# CanBus12apr.net
KiCad netlist of a schematic drawn in EAGLE
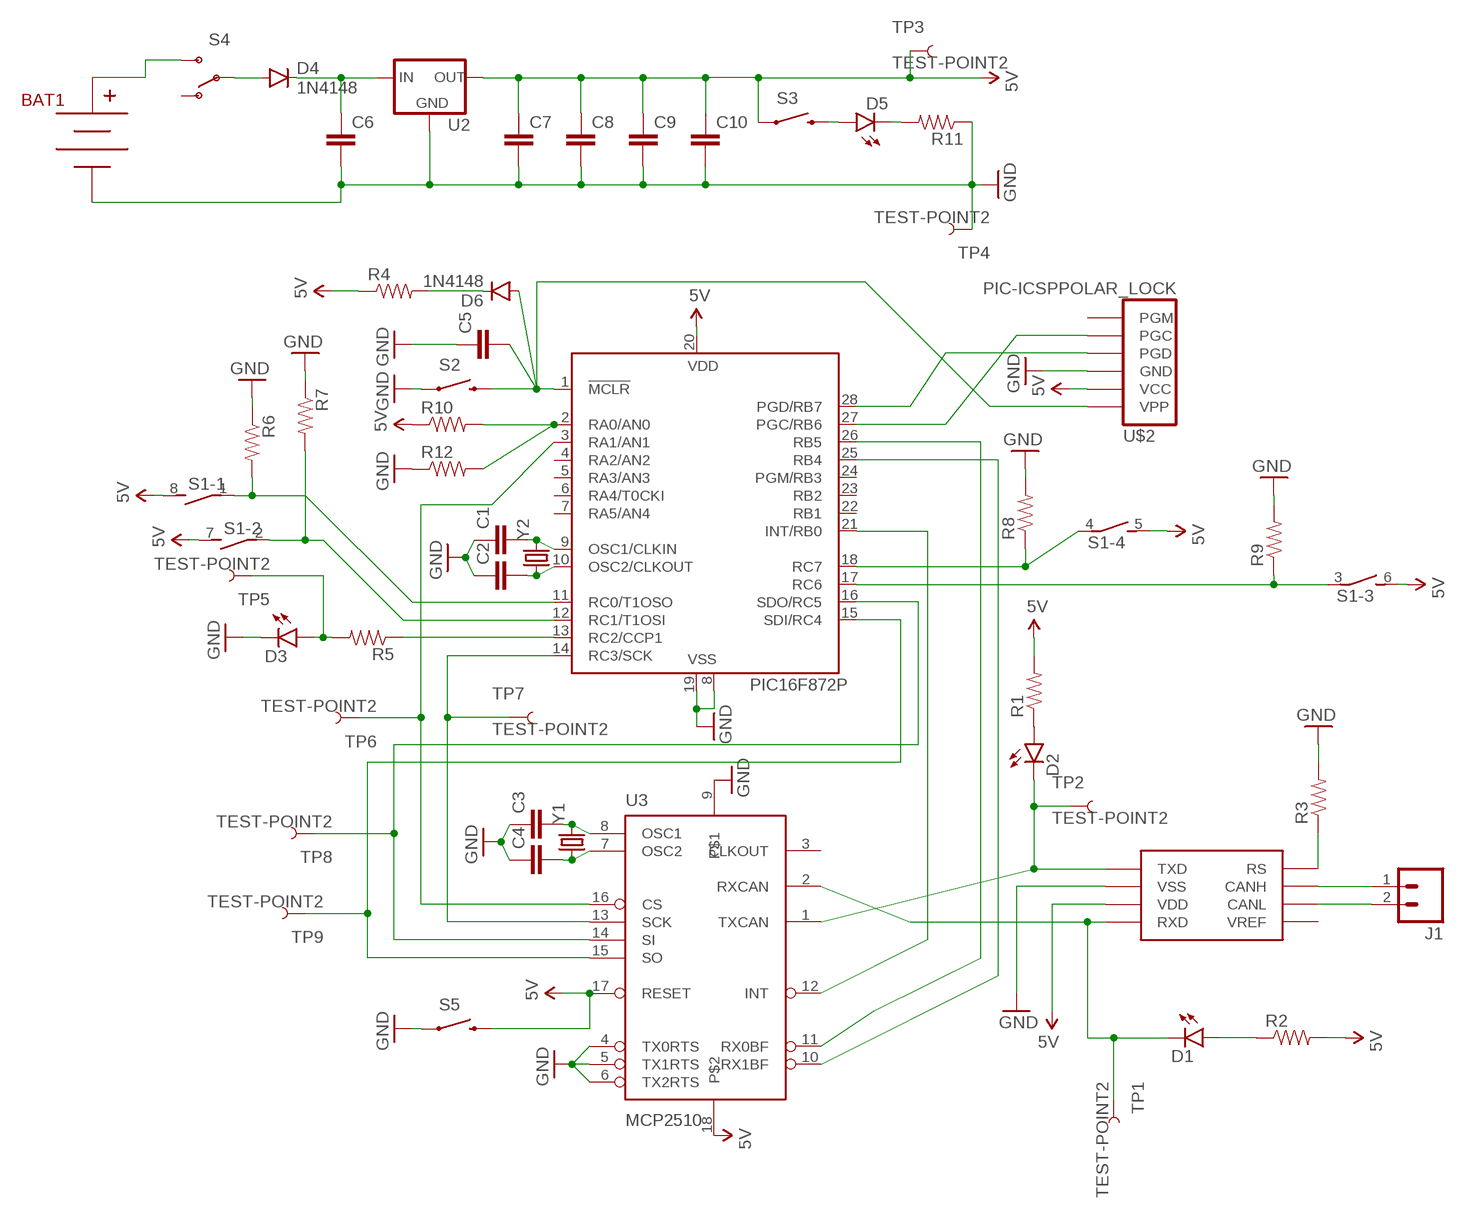
[diagram p0: schematic, sheet 1]

(export (version "E")
  (design (tool "Eeschema 10.0.6"))
  (components
    (comp (ref "BAT1")
      (value "BC9VPC")
      (footprint "eagle-import:BC9VPC")
      (libsource (lib "eagle-import") (part "BC9VPC"))
    )
    (comp (ref "C1")
      (value "CAPPTH")
      (footprint "eagle-import:CAP-PTH-SMALL")
      (libsource (lib "eagle-import") (part "CAPPTH"))
    )
    (comp (ref "C2")
      (value "CAPPTH")
      (footprint "eagle-import:CAP-PTH-SMALL")
      (libsource (lib "eagle-import") (part "CAPPTH"))
    )
    (comp (ref "C3")
      (value "CAPPTH")
      (footprint "eagle-import:CAP-PTH-SMALL")
      (libsource (lib "eagle-import") (part "CAPPTH"))
    )
    (comp (ref "C4")
      (value "CAPPTH")
      (footprint "eagle-import:CAP-PTH-SMALL")
      (libsource (lib "eagle-import") (part "CAPPTH"))
    )
    (comp (ref "C5")
      (value "CAPPTH")
      (footprint "eagle-import:CAP-PTH-SMALL")
      (libsource (lib "eagle-import") (part "CAPPTH"))
    )
    (comp (ref "C6")
      (value "CAPPTH")
      (footprint "eagle-import:CAP-PTH-SMALL")
      (libsource (lib "eagle-import") (part "CAPPTH"))
    )
    (comp (ref "C7")
      (value "CAPPTH")
      (footprint "eagle-import:CAP-PTH-SMALL")
      (libsource (lib "eagle-import") (part "CAPPTH"))
    )
    (comp (ref "C8")
      (value "CAPPTH")
      (footprint "eagle-import:CAP-PTH-SMALL")
      (libsource (lib "eagle-import") (part "CAPPTH"))
    )
    (comp (ref "C9")
      (value "CAPPTH")
      (footprint "eagle-import:CAP-PTH-SMALL")
      (libsource (lib "eagle-import") (part "CAPPTH"))
    )
    (comp (ref "C10")
      (value "CAPPTH")
      (footprint "eagle-import:CAP-PTH-SMALL")
      (libsource (lib "eagle-import") (part "CAPPTH"))
    )
    (comp (ref "D1")
      (value "LED5MM")
      (footprint "eagle-import:LED5MM")
      (libsource (lib "eagle-import") (part "LED5MM"))
    )
    (comp (ref "D2")
      (value "LED5MM")
      (footprint "eagle-import:LED5MM")
      (libsource (lib "eagle-import") (part "LED5MM"))
    )
    (comp (ref "D3")
      (value "LED5MM")
      (footprint "eagle-import:LED5MM")
      (libsource (lib "eagle-import") (part "LED5MM"))
    )
    (comp (ref "D4")
      (value "1N4148")
      (footprint "eagle-import:DIODE-1N4148-KIT")
      (libsource (lib "eagle-import") (part "DIODEKIT"))
    )
    (comp (ref "D5")
      (value "LED5MM")
      (footprint "eagle-import:LED5MM")
      (libsource (lib "eagle-import") (part "LED5MM"))
    )
    (comp (ref "D6")
      (value "1N4148")
      (footprint "eagle-import:DIODE-1N4148-KIT")
      (libsource (lib "eagle-import") (part "DIODEKIT"))
    )
    (comp (ref "IC1")
      (value "PIC16F872P")
      (footprint "eagle-import:DIL28-3")
      (fields (field (name "MF") "MICROCHIP") (field (name "MPN") "PIC16F872-I/SP"))
      (libsource (lib "eagle-import") (part "PIC16872PF"))
    )
    (comp (ref "J1")
      (value "M02PTH")
      (footprint "eagle-import:1X02")
      (libsource (lib "eagle-import") (part "M02PTH"))
    )
    (comp (ref "R1")
      (value "RESISTOREZ")
      (footprint "eagle-import:AXIAL-0.3EZ")
      (libsource (lib "eagle-import") (part "RESISTOREZ"))
    )
    (comp (ref "R2")
      (value "RESISTOREZ")
      (footprint "eagle-import:AXIAL-0.3EZ")
      (libsource (lib "eagle-import") (part "RESISTOREZ"))
    )
    (comp (ref "R3")
      (value "RESISTOREZ")
      (footprint "eagle-import:AXIAL-0.3EZ")
      (libsource (lib "eagle-import") (part "RESISTOREZ"))
    )
    (comp (ref "R4")
      (value "RESISTOREZ")
      (footprint "eagle-import:AXIAL-0.3EZ")
      (libsource (lib "eagle-import") (part "RESISTOREZ"))
    )
    (comp (ref "R5")
      (value "RESISTOREZ")
      (footprint "eagle-import:AXIAL-0.3EZ")
      (libsource (lib "eagle-import") (part "RESISTOREZ"))
    )
    (comp (ref "R6")
      (value "RESISTOREZ")
      (footprint "eagle-import:AXIAL-0.3EZ")
      (libsource (lib "eagle-import") (part "RESISTOREZ"))
    )
    (comp (ref "R7")
      (value "RESISTOREZ")
      (footprint "eagle-import:AXIAL-0.3EZ")
      (libsource (lib "eagle-import") (part "RESISTOREZ"))
    )
    (comp (ref "R8")
      (value "RESISTOREZ")
      (footprint "eagle-import:AXIAL-0.3EZ")
      (libsource (lib "eagle-import") (part "RESISTOREZ"))
    )
    (comp (ref "R9")
      (value "RESISTOREZ")
      (footprint "eagle-import:AXIAL-0.3EZ")
      (libsource (lib "eagle-import") (part "RESISTOREZ"))
    )
    (comp (ref "R10")
      (value "RESISTOREZ")
      (footprint "eagle-import:AXIAL-0.3EZ")
      (libsource (lib "eagle-import") (part "RESISTOREZ"))
    )
    (comp (ref "R11")
      (value "RESISTOREZ")
      (footprint "eagle-import:AXIAL-0.3EZ")
      (libsource (lib "eagle-import") (part "RESISTOREZ"))
    )
    (comp (ref "R12")
      (value "RESISTORAXIAL-0.3")
      (footprint "eagle-import:AXIAL-0.3")
      (libsource (lib "eagle-import") (part "SparkFun-Resistors_RESISTORAXIAL-0.3"))
    )
    (comp (ref "S1")
      (value "DIP04S")
      (footprint "eagle-import:DIP04S")
      (libsource (lib "eagle-import") (part "DIP04S"))
    )
    (comp (ref "S2")
      (value "SWITCH-MOMENTARY-2PTH")
      (footprint "eagle-import:TACTILE-PTH")
      (libsource (lib "eagle-import") (part "SWITCH-MOMENTARY-2PTH"))
    )
    (comp (ref "S3")
      (value "SWITCH-MOMENTARY-2PTH")
      (footprint "eagle-import:TACTILE-PTH")
      (libsource (lib "eagle-import") (part "SWITCH-MOMENTARY-2PTH"))
    )
    (comp (ref "S4")
      (value "SWITCH-SPDTKIT")
      (footprint "eagle-import:SWITCH-SPDT_KIT")
      (libsource (lib "eagle-import") (part "SWITCH-SPDTKIT"))
    )
    (comp (ref "S5")
      (value "SWITCH-MOMENTARY-2PTH")
      (footprint "eagle-import:TACTILE-PTH")
      (libsource (lib "eagle-import") (part "SWITCH-MOMENTARY-2PTH"))
    )
    (comp (ref "TP1")
      (value "TEST-POINT2")
      (footprint "eagle-import:PAD.02X.02")
      (libsource (lib "eagle-import") (part "TEST-POINT2"))
    )
    (comp (ref "TP2")
      (value "TEST-POINT2")
      (footprint "eagle-import:PAD.02X.02")
      (libsource (lib "eagle-import") (part "TEST-POINT2"))
    )
    (comp (ref "TP3")
      (value "TEST-POINT2")
      (footprint "eagle-import:PAD.02X.02")
      (libsource (lib "eagle-import") (part "TEST-POINT2"))
    )
    (comp (ref "TP4")
      (value "TEST-POINT2")
      (footprint "eagle-import:PAD.02X.02")
      (libsource (lib "eagle-import") (part "TEST-POINT2"))
    )
    (comp (ref "TP5")
      (value "TEST-POINT2")
      (footprint "eagle-import:PAD.02X.02")
      (libsource (lib "eagle-import") (part "TEST-POINT2"))
    )
    (comp (ref "TP6")
      (value "TEST-POINT2")
      (footprint "eagle-import:PAD.02X.02")
      (libsource (lib "eagle-import") (part "TEST-POINT2"))
    )
    (comp (ref "TP7")
      (value "TEST-POINT2")
      (footprint "eagle-import:PAD.02X.02")
      (libsource (lib "eagle-import") (part "TEST-POINT2"))
    )
    (comp (ref "TP8")
      (value "TEST-POINT2")
      (footprint "eagle-import:PAD.02X.02")
      (libsource (lib "eagle-import") (part "TEST-POINT2"))
    )
    (comp (ref "TP9")
      (value "TEST-POINT2")
      (footprint "eagle-import:PAD.02X.02")
      (libsource (lib "eagle-import") (part "TEST-POINT2"))
    )
    (comp (ref "U$1")
      (value "MCP2551")
      (footprint "eagle-import:MCP2551")
      (libsource (lib "eagle-import") (part "MCP2551"))
    )
    (comp (ref "U$2")
      (value "PIC-ICSPPOLAR_LOCK")
      (footprint "eagle-import:MOLEX-1X6_LOCK")
      (libsource (lib "eagle-import") (part "PIC-ICSPPOLAR_LOCK"))
    )
    (comp (ref "U2")
      (value "V_REG_78XXSIDE")
      (footprint "eagle-import:78XXL")
      (libsource (lib "eagle-import") (part "V_REG_78XXSIDE"))
    )
    (comp (ref "U3")
      (value "MCP2510")
      (footprint "eagle-import:DIL18")
      (libsource (lib "eagle-import") (part "MCP2510"))
    )
    (comp (ref "Y1")
      (value "CRYSTALHC49UV")
      (footprint "eagle-import:HC49U-V")
      (libsource (lib "eagle-import") (part "CRYSTALHC49UV"))
    )
    (comp (ref "Y2")
      (value "CRYSTALHC49UV")
      (footprint "eagle-import:HC49U-V")
      (libsource (lib "eagle-import") (part "CRYSTALHC49UV"))
    )
  )
  (nets
    (net (code "1") (name "5V") (class "Default")
      (node (ref "C10") (pin "1") (pinfunction "1_1") (pintype "passive"))
      (node (ref "C7") (pin "1") (pinfunction "1_1") (pintype "passive"))
      (node (ref "C8") (pin "1") (pinfunction "1_1") (pintype "passive"))
      (node (ref "C9") (pin "1") (pinfunction "1_1") (pintype "passive"))
      (node (ref "IC1") (pin "20") (pinfunction "VDD_20") (pintype "power_in"))
      (node (ref "R1") (pin "P$2") (pinfunction "2_P$2") (pintype "passive"))
      (node (ref "R10") (pin "P$1") (pinfunction "1_P$1") (pintype "passive"))
      (node (ref "R2") (pin "P$2") (pinfunction "2_P$2") (pintype "passive"))
      (node (ref "R4") (pin "P$1") (pinfunction "1_P$1") (pintype "passive"))
      (node (ref "S1") (pin "5") (pinfunction "2_5") (pintype "passive"))
      (node (ref "S1") (pin "6") (pinfunction "2_6") (pintype "passive"))
      (node (ref "S1") (pin "7") (pinfunction "2_7") (pintype "passive"))
      (node (ref "S1") (pin "8") (pinfunction "2_8") (pintype "passive"))
      (node (ref "S3") (pin "1") (pinfunction "1_1") (pintype "passive"))
      (node (ref "S5") (pin "3") (pinfunction "2_3") (pintype "passive"))
      (node (ref "TP3") (pin "P$1") (pinfunction "1_P$1") (pintype "bidirectional"))
      (node (ref "U$1") (pin "VDD") (pinfunction "VDD_VDD") (pintype "bidirectional"))
      (node (ref "U$2") (pin "5") (pinfunction "VCC_5") (pintype "bidirectional"))
      (node (ref "U2") (pin "OUT") (pinfunction "OUT_OUT") (pintype "passive"))
      (node (ref "U3") (pin "17") (pinfunction "RESET_17") (pintype "input"))
      (node (ref "U3") (pin "18") (pinfunction "P$2_18") (pintype "bidirectional"))
    )
    (net (code "2") (name "GND") (class "Default")
      (node (ref "BAT1") (pin "V-") (pinfunction "V-_V-") (pintype "bidirectional"))
      (node (ref "C1") (pin "1") (pinfunction "1_1") (pintype "passive"))
      (node (ref "C10") (pin "2") (pinfunction "2_2") (pintype "passive"))
      (node (ref "C2") (pin "1") (pinfunction "1_1") (pintype "passive"))
      (node (ref "C3") (pin "1") (pinfunction "1_1") (pintype "passive"))
      (node (ref "C4") (pin "1") (pinfunction "1_1") (pintype "passive"))
      (node (ref "C5") (pin "1") (pinfunction "1_1") (pintype "passive"))
      (node (ref "C6") (pin "2") (pinfunction "2_2") (pintype "passive"))
      (node (ref "C7") (pin "2") (pinfunction "2_2") (pintype "passive"))
      (node (ref "C8") (pin "2") (pinfunction "2_2") (pintype "passive"))
      (node (ref "C9") (pin "2") (pinfunction "2_2") (pintype "passive"))
      (node (ref "D3") (pin "K") (pinfunction "C_K") (pintype "passive"))
      (node (ref "IC1") (pin "19") (pinfunction "VSS_19") (pintype "power_in"))
      (node (ref "IC1") (pin "8") (pinfunction "VSS_8") (pintype "power_in"))
      (node (ref "R11") (pin "P$1") (pinfunction "1_P$1") (pintype "passive"))
      (node (ref "R12") (pin "P$1") (pinfunction "1_P$1") (pintype "passive"))
      (node (ref "R3") (pin "P$2") (pinfunction "2_P$2") (pintype "passive"))
      (node (ref "R6") (pin "P$1") (pinfunction "1_P$1") (pintype "passive"))
      (node (ref "R7") (pin "P$1") (pinfunction "1_P$1") (pintype "passive"))
      (node (ref "R8") (pin "P$2") (pinfunction "2_P$2") (pintype "passive"))
      (node (ref "R9") (pin "P$2") (pinfunction "2_P$2") (pintype "passive"))
      (node (ref "S2") (pin "1") (pinfunction "1_1") (pintype "passive"))
      (node (ref "S5") (pin "1") (pinfunction "1_1") (pintype "passive"))
      (node (ref "TP4") (pin "P$1") (pinfunction "1_P$1") (pintype "bidirectional"))
      (node (ref "U$1") (pin "VSS") (pinfunction "VSS_VSS") (pintype "bidirectional"))
      (node (ref "U$2") (pin "4") (pinfunction "GND_4") (pintype "bidirectional"))
      (node (ref "U2") (pin "GND") (pinfunction "GND_GND") (pintype "input"))
      (node (ref "U3") (pin "4") (pinfunction "TX0RTS_4") (pintype "input"))
      (node (ref "U3") (pin "5") (pinfunction "TX1RTS_5") (pintype "input"))
      (node (ref "U3") (pin "6") (pinfunction "TX2RTS_6") (pintype "input"))
      (node (ref "U3") (pin "9") (pinfunction "P$1_9") (pintype "bidirectional"))
    )
    (net (code "3") (name "Net-(C6-Pad1)") (class "Default")
      (node (ref "C6") (pin "1") (pinfunction "1_1") (pintype "passive"))
      (node (ref "D4") (pin "C") (pinfunction "C_C") (pintype "passive"))
      (node (ref "U2") (pin "IN") (pinfunction "IN_IN") (pintype "input"))
    )
    (net (code "4") (name "Net-(D1-C)") (class "Default")
      (node (ref "D1") (pin "K") (pinfunction "C_K") (pintype "passive"))
      (node (ref "TP1") (pin "P$1") (pinfunction "1_P$1") (pintype "bidirectional"))
      (node (ref "U$1") (pin "RXD") (pinfunction "RXD_RXD") (pintype "bidirectional"))
      (node (ref "U3") (pin "2") (pinfunction "RXCAN_2") (pintype "input"))
    )
    (net (code "5") (name "Net-(D2-C)") (class "Default")
      (node (ref "D2") (pin "K") (pinfunction "C_K") (pintype "passive"))
      (node (ref "TP2") (pin "P$1") (pinfunction "1_P$1") (pintype "bidirectional"))
      (node (ref "U$1") (pin "TXD") (pinfunction "TXD_TXD") (pintype "bidirectional"))
      (node (ref "U3") (pin "1") (pinfunction "TXCAN_1") (pintype "output"))
    )
    (net (code "6") (name "Net-(D5-C)") (class "Default")
      (node (ref "D5") (pin "K") (pinfunction "C_K") (pintype "passive"))
      (node (ref "R11") (pin "P$2") (pinfunction "2_P$2") (pintype "passive"))
    )
    (net (code "7") (name "Net-(IC1-INT{slash}RB0)") (class "Default")
      (node (ref "IC1") (pin "21") (pinfunction "INT/RB0_21") (pintype "bidirectional"))
      (node (ref "U3") (pin "12") (pinfunction "INT_12") (pintype "output"))
    )
    (net (code "8") (name "Net-(IC1-OSC1{slash}CLKIN)") (class "Default")
      (node (ref "C1") (pin "2") (pinfunction "2_2") (pintype "passive"))
      (node (ref "IC1") (pin "9") (pinfunction "OSC1/CLKIN_9") (pintype "input"))
      (node (ref "Y2") (pin "2") (pinfunction "2_2") (pintype "passive"))
    )
    (net (code "9") (name "Net-(IC1-OSC2{slash}CLKOUT)") (class "Default")
      (node (ref "C2") (pin "2") (pinfunction "2_2") (pintype "passive"))
      (node (ref "IC1") (pin "10") (pinfunction "OSC2/CLKOUT_10") (pintype "output"))
      (node (ref "Y2") (pin "1") (pinfunction "1_1") (pintype "passive"))
    )
    (net (code "10") (name "Net-(IC1-PGC{slash}RB6)") (class "Default")
      (node (ref "IC1") (pin "27") (pinfunction "PGC/RB6_27") (pintype "bidirectional"))
      (node (ref "U$2") (pin "2") (pinfunction "PGC_2") (pintype "bidirectional"))
    )
    (net (code "11") (name "Net-(IC1-PGD{slash}RB7)") (class "Default")
      (node (ref "IC1") (pin "28") (pinfunction "PGD/RB7_28") (pintype "bidirectional"))
      (node (ref "U$2") (pin "3") (pinfunction "PGD_3") (pintype "bidirectional"))
    )
    (net (code "12") (name "Net-(IC1-RA0{slash}AN0)") (class "Default")
      (node (ref "IC1") (pin "2") (pinfunction "RA0/AN0_2") (pintype "bidirectional"))
      (node (ref "R10") (pin "P$2") (pinfunction "2_P$2") (pintype "passive"))
      (node (ref "R12") (pin "P$2") (pinfunction "2_P$2") (pintype "passive"))
    )
    (net (code "13") (name "Net-(IC1-RA1{slash}AN1)") (class "Default")
      (node (ref "IC1") (pin "3") (pinfunction "RA1/AN1_3") (pintype "bidirectional"))
      (node (ref "TP6") (pin "P$1") (pinfunction "1_P$1") (pintype "bidirectional"))
      (node (ref "U3") (pin "16") (pinfunction "CS_16") (pintype "input"))
    )
    (net (code "14") (name "Net-(IC1-RB4)") (class "Default")
      (node (ref "IC1") (pin "25") (pinfunction "RB4_25") (pintype "bidirectional"))
      (node (ref "U3") (pin "10") (pinfunction "RX1BF_10") (pintype "output"))
    )
    (net (code "15") (name "Net-(IC1-RB5)") (class "Default")
      (node (ref "IC1") (pin "26") (pinfunction "RB5_26") (pintype "bidirectional"))
      (node (ref "U3") (pin "11") (pinfunction "RX0BF_11") (pintype "output"))
    )
    (net (code "16") (name "Net-(IC1-RC0{slash}T1OSO)") (class "Default")
      (node (ref "IC1") (pin "11") (pinfunction "RC0/T1OSO_11") (pintype "bidirectional"))
      (node (ref "R6") (pin "P$2") (pinfunction "2_P$2") (pintype "passive"))
      (node (ref "S1") (pin "1") (pinfunction "1_1") (pintype "passive"))
    )
    (net (code "17") (name "Net-(IC1-RC1{slash}T1OSI)") (class "Default")
      (node (ref "IC1") (pin "12") (pinfunction "RC1/T1OSI_12") (pintype "bidirectional"))
      (node (ref "R7") (pin "P$2") (pinfunction "2_P$2") (pintype "passive"))
      (node (ref "S1") (pin "2") (pinfunction "1_2") (pintype "passive"))
    )
    (net (code "18") (name "Net-(IC1-RC2{slash}CCP1)") (class "Default")
      (node (ref "IC1") (pin "13") (pinfunction "RC2/CCP1_13") (pintype "bidirectional"))
      (node (ref "R5") (pin "P$1") (pinfunction "1_P$1") (pintype "passive"))
    )
    (net (code "19") (name "Net-(IC1-RC3{slash}SCK)") (class "Default")
      (node (ref "IC1") (pin "14") (pinfunction "RC3/SCK_14") (pintype "bidirectional"))
      (node (ref "TP7") (pin "P$1") (pinfunction "1_P$1") (pintype "bidirectional"))
      (node (ref "U3") (pin "13") (pinfunction "SCK_13") (pintype "input"))
    )
    (net (code "20") (name "Net-(IC1-RC6)") (class "Default")
      (node (ref "IC1") (pin "17") (pinfunction "RC6_17") (pintype "bidirectional"))
      (node (ref "R9") (pin "P$1") (pinfunction "1_P$1") (pintype "passive"))
      (node (ref "S1") (pin "3") (pinfunction "1_3") (pintype "passive"))
    )
    (net (code "21") (name "Net-(IC1-RC7)") (class "Default")
      (node (ref "IC1") (pin "18") (pinfunction "RC7_18") (pintype "bidirectional"))
      (node (ref "R8") (pin "P$1") (pinfunction "1_P$1") (pintype "passive"))
      (node (ref "S1") (pin "4") (pinfunction "1_4") (pintype "passive"))
    )
    (net (code "22") (name "Net-(IC1-SDI{slash}RC4)") (class "Default")
      (node (ref "IC1") (pin "15") (pinfunction "SDI/RC4_15") (pintype "bidirectional"))
      (node (ref "TP9") (pin "P$1") (pinfunction "1_P$1") (pintype "bidirectional"))
      (node (ref "U3") (pin "15") (pinfunction "SO_15") (pintype "output"))
    )
    (net (code "23") (name "Net-(IC1-SDO{slash}RC5)") (class "Default")
      (node (ref "IC1") (pin "16") (pinfunction "SDO/RC5_16") (pintype "bidirectional"))
      (node (ref "TP8") (pin "P$1") (pinfunction "1_P$1") (pintype "bidirectional"))
      (node (ref "U3") (pin "14") (pinfunction "SI_14") (pintype "input"))
    )
    (net (code "24") (name "Net-(IC1-~{MCLR})") (class "Default")
      (node (ref "C5") (pin "2") (pinfunction "2_2") (pintype "passive"))
      (node (ref "D6") (pin "A") (pinfunction "A_A") (pintype "passive"))
      (node (ref "IC1") (pin "1") (pinfunction "~{MCLR}_1") (pintype "input"))
      (node (ref "S2") (pin "3") (pinfunction "2_3") (pintype "passive"))
      (node (ref "U$2") (pin "6") (pinfunction "VPP_6") (pintype "bidirectional"))
    )
    (net (code "25") (name "Net-(J1-Pad1)") (class "Default")
      (node (ref "J1") (pin "1") (pinfunction "1_1") (pintype "passive"))
      (node (ref "U$1") (pin "CANH") (pinfunction "CANH_CANH") (pintype "bidirectional"))
    )
    (net (code "26") (name "Net-(J1-Pad2)") (class "Default")
      (node (ref "J1") (pin "2") (pinfunction "2_2") (pintype "passive"))
      (node (ref "U$1") (pin "CANL") (pinfunction "CANL_CANL") (pintype "bidirectional"))
    )
    (net (code "27") (name "Net-(R1-1)") (class "Default")
      (node (ref "D2") (pin "A") (pinfunction "A_A") (pintype "passive"))
      (node (ref "R1") (pin "P$1") (pinfunction "1_P$1") (pintype "passive"))
    )
    (net (code "28") (name "Net-(R2-1)") (class "Default")
      (node (ref "D1") (pin "A") (pinfunction "A_A") (pintype "passive"))
      (node (ref "R2") (pin "P$1") (pinfunction "1_P$1") (pintype "passive"))
    )
    (net (code "29") (name "Net-(R3-1)") (class "Default")
      (node (ref "R3") (pin "P$1") (pinfunction "1_P$1") (pintype "passive"))
      (node (ref "U$1") (pin "RS") (pinfunction "RS_RS") (pintype "bidirectional"))
    )
    (net (code "30") (name "Net-(R4-2)") (class "Default")
      (node (ref "D6") (pin "C") (pinfunction "C_C") (pintype "passive"))
      (node (ref "R4") (pin "P$2") (pinfunction "2_P$2") (pintype "passive"))
    )
    (net (code "31") (name "Net-(R5-2)") (class "Default")
      (node (ref "D3") (pin "A") (pinfunction "A_A") (pintype "passive"))
      (node (ref "R5") (pin "P$2") (pinfunction "2_P$2") (pintype "passive"))
      (node (ref "TP5") (pin "P$1") (pinfunction "1_P$1") (pintype "bidirectional"))
    )
    (net (code "32") (name "Net-(S3-2)") (class "Default")
      (node (ref "D5") (pin "A") (pinfunction "A_A") (pintype "passive"))
      (node (ref "S3") (pin "3") (pinfunction "2_3") (pintype "passive"))
    )
    (net (code "33") (name "Net-(S4-P)") (class "Default")
      (node (ref "D4") (pin "A") (pinfunction "A_A") (pintype "passive"))
      (node (ref "S4") (pin "2") (pinfunction "P_2") (pintype "passive"))
    )
    (net (code "34") (name "Net-(S4-S)") (class "Default")
      (node (ref "BAT1") (pin "V+") (pinfunction "V+_V+") (pintype "bidirectional"))
      (node (ref "S4") (pin "3") (pinfunction "S_3") (pintype "passive"))
    )
    (net (code "35") (name "Net-(U3-OSC1)") (class "Default")
      (node (ref "C3") (pin "2") (pinfunction "2_2") (pintype "passive"))
      (node (ref "U3") (pin "8") (pinfunction "OSC1_8") (pintype "input"))
      (node (ref "Y1") (pin "2") (pinfunction "2_2") (pintype "passive"))
    )
    (net (code "36") (name "Net-(U3-OSC2)") (class "Default")
      (node (ref "C4") (pin "2") (pinfunction "2_2") (pintype "passive"))
      (node (ref "U3") (pin "7") (pinfunction "OSC2_7") (pintype "output"))
      (node (ref "Y1") (pin "1") (pinfunction "1_1") (pintype "passive"))
    )
    (net (code "37") (name "unconnected-(IC1-PGM{slash}RB3-Pad24)") (class "Default")
      (node (ref "IC1") (pin "24") (pinfunction "PGM/RB3_24") (pintype "bidirectional"))
    )
    (net (code "38") (name "unconnected-(IC1-RA2{slash}AN2-Pad4)") (class "Default")
      (node (ref "IC1") (pin "4") (pinfunction "RA2/AN2_4") (pintype "bidirectional"))
    )
    (net (code "39") (name "unconnected-(IC1-RA3{slash}AN3-Pad5)") (class "Default")
      (node (ref "IC1") (pin "5") (pinfunction "RA3/AN3_5") (pintype "bidirectional"))
    )
    (net (code "40") (name "unconnected-(IC1-RA4{slash}T0CKI-Pad6)") (class "Default")
      (node (ref "IC1") (pin "6") (pinfunction "RA4/T0CKI_6") (pintype "bidirectional"))
    )
    (net (code "41") (name "unconnected-(IC1-RA5{slash}AN4-Pad7)") (class "Default")
      (node (ref "IC1") (pin "7") (pinfunction "RA5/AN4_7") (pintype "bidirectional"))
    )
    (net (code "42") (name "unconnected-(IC1-RB1-Pad22)") (class "Default")
      (node (ref "IC1") (pin "22") (pinfunction "RB1_22") (pintype "bidirectional"))
    )
    (net (code "43") (name "unconnected-(IC1-RB2-Pad23)") (class "Default")
      (node (ref "IC1") (pin "23") (pinfunction "RB2_23") (pintype "bidirectional"))
    )
    (net (code "44") (name "unconnected-(S4-O-Pad1)") (class "Default")
      (node (ref "S4") (pin "1") (pinfunction "O_1") (pintype "passive"))
    )
    (net (code "45") (name "unconnected-(U$1-PadVREF)") (class "Default")
      (node (ref "U$1") (pin "VREF") (pinfunction "VREF_VREF") (pintype "bidirectional"))
    )
    (net (code "46") (name "unconnected-(U$2-PGM-Pad1)") (class "Default")
      (node (ref "U$2") (pin "1") (pinfunction "PGM_1") (pintype "bidirectional"))
    )
    (net (code "47") (name "unconnected-(U3-CLKOUT-Pad3)") (class "Default")
      (node (ref "U3") (pin "3") (pinfunction "CLKOUT_3") (pintype "output"))
    )
  )
)
